# main.net
KiCad netlist of a schematic drawn in EAGLE
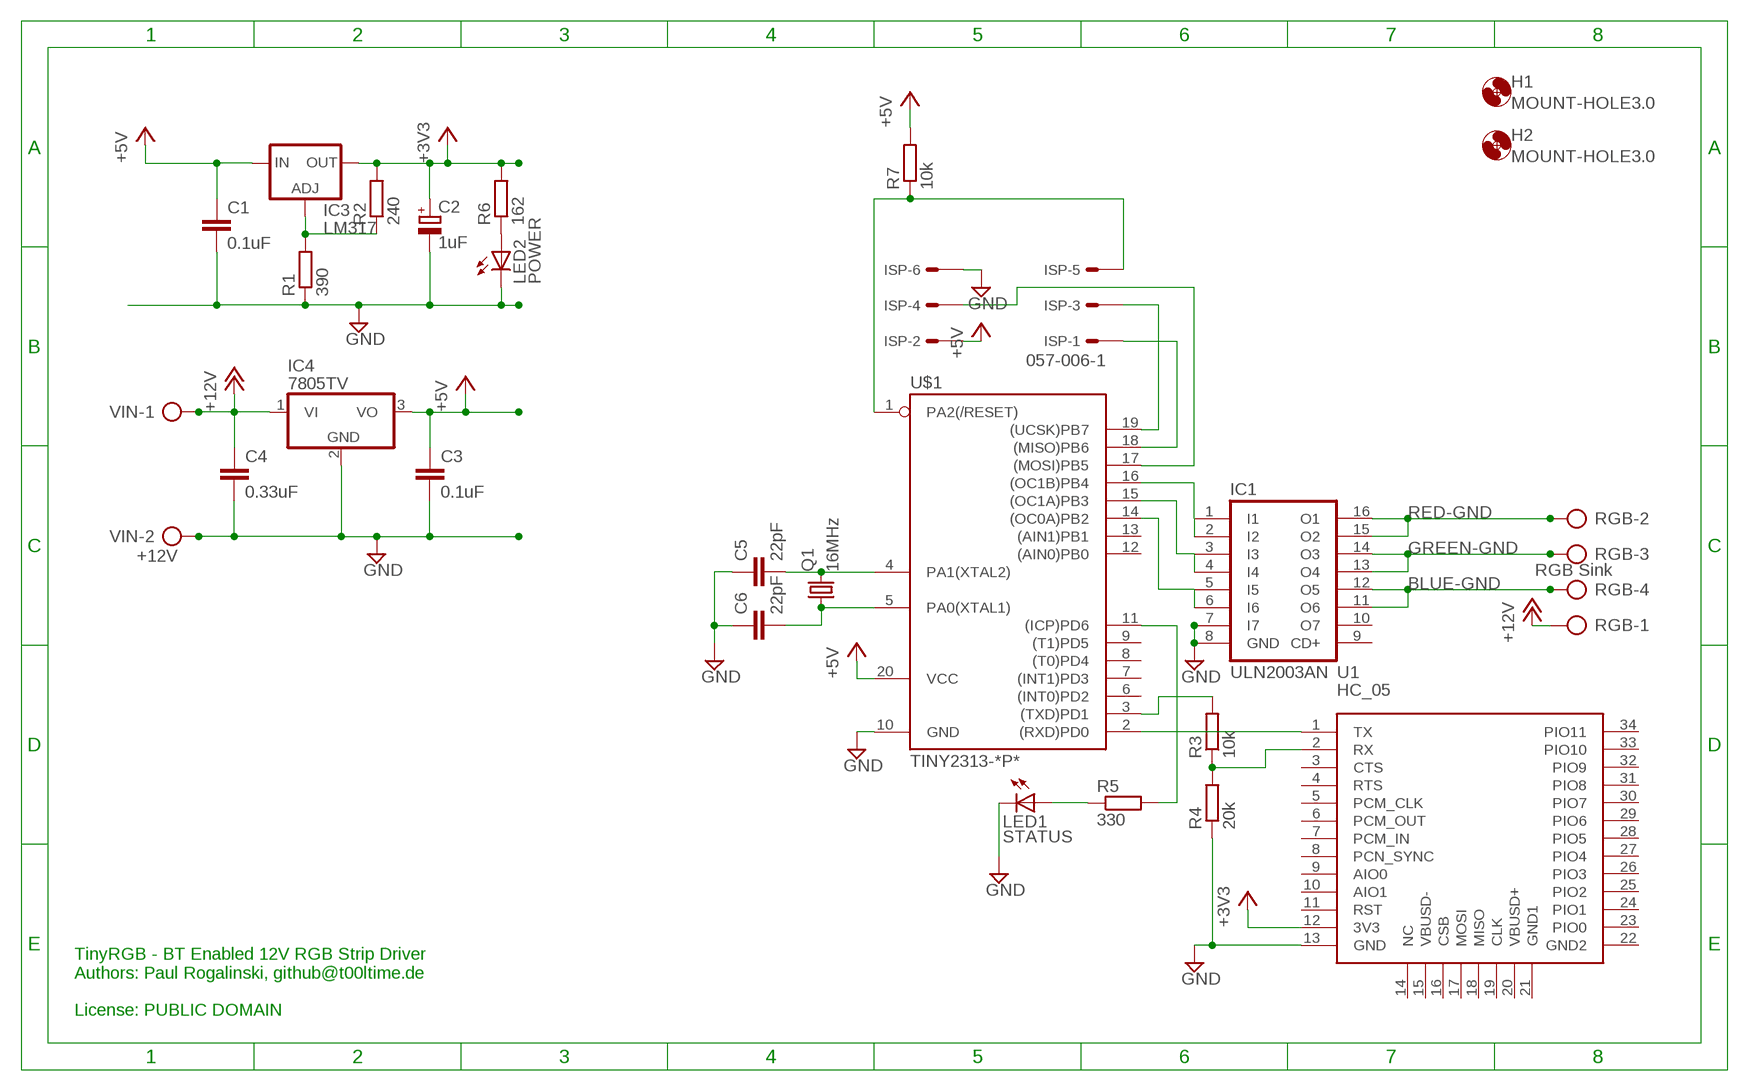
[diagram p0: schematic, sheet 1]

(export (version "E")
  (design (tool "Eeschema 10.0.6"))
  (components
    (comp (ref "C1")
      (value "0.1uF")
      (footprint "eagle-import:C025-025X050")
      (libsource (lib "eagle-import") (part "C-EU025-025X050"))
    )
    (comp (ref "C2")
      (value "1uF")
      (footprint "eagle-import:E2-5")
      (libsource (lib "eagle-import") (part "CPOL-EUE2-5"))
    )
    (comp (ref "C3")
      (value "0.1uF")
      (footprint "eagle-import:C025-025X050")
      (libsource (lib "eagle-import") (part "C-EU025-025X050"))
    )
    (comp (ref "C4")
      (value "0.33uF")
      (footprint "eagle-import:C025_050-025X075")
      (libsource (lib "eagle-import") (part "C-EU025_050-025X075"))
    )
    (comp (ref "C5")
      (value "22pF")
      (footprint "eagle-import:C025-024X044")
      (libsource (lib "eagle-import") (part "C-EU025-024X044"))
    )
    (comp (ref "C6")
      (value "22pF")
      (footprint "eagle-import:C025-024X044")
      (libsource (lib "eagle-import") (part "C-EU025-024X044"))
    )
    (comp (ref "H1")
      (value "MOUNT-HOLE3.0")
      (footprint "eagle-import:3,0")
      (libsource (lib "eagle-import") (part "MOUNT-HOLE3.0"))
    )
    (comp (ref "H2")
      (value "MOUNT-HOLE3.0")
      (footprint "eagle-import:3,0")
      (libsource (lib "eagle-import") (part "MOUNT-HOLE3.0"))
    )
    (comp (ref "IC1")
      (value "ULN2003AN")
      (footprint "eagle-import:DIL16")
      (libsource (lib "eagle-import") (part "ULN2003AN"))
    )
    (comp (ref "IC3")
      (value "LM317")
      (footprint "eagle-import:317L")
      (libsource (lib "eagle-import") (part "LM317L"))
    )
    (comp (ref "IC4")
      (value "7805TV")
      (footprint "eagle-import:TO220V")
      (libsource (lib "eagle-import") (part "78TV05"))
    )
    (comp (ref "ISP")
      (value "057-006-1")
      (footprint "eagle-import:057-006-1")
      (libsource (lib "eagle-import") (part "057-006-1"))
    )
    (comp (ref "LED1")
      (value "STATUS")
      (footprint "eagle-import:LED3MM")
      (libsource (lib "eagle-import") (part "LED3MM"))
    )
    (comp (ref "LED2")
      (value "POWER")
      (footprint "eagle-import:LED3MM")
      (libsource (lib "eagle-import") (part "LED3MM"))
    )
    (comp (ref "Q1")
      (value "16MHz")
      (footprint "eagle-import:HC49U-V")
      (libsource (lib "eagle-import") (part "CRYSTALHC49U-V"))
    )
    (comp (ref "R1")
      (value "390")
      (footprint "eagle-import:0207_5V")
      (libsource (lib "eagle-import") (part "R-EU_0207/5V"))
    )
    (comp (ref "R2")
      (value "240")
      (footprint "eagle-import:0207_5V")
      (libsource (lib "eagle-import") (part "R-EU_0207/5V"))
    )
    (comp (ref "R3")
      (value "10k")
      (footprint "eagle-import:0207_5V")
      (libsource (lib "eagle-import") (part "R-EU_0207/5V"))
    )
    (comp (ref "R4")
      (value "20k")
      (footprint "eagle-import:0207_5V")
      (libsource (lib "eagle-import") (part "R-EU_0207/5V"))
    )
    (comp (ref "R5")
      (value "330")
      (footprint "eagle-import:0207_5V")
      (libsource (lib "eagle-import") (part "R-EU_0207/5V"))
    )
    (comp (ref "R6")
      (value "162")
      (footprint "eagle-import:0207_5V")
      (libsource (lib "eagle-import") (part "R-EU_0207/5V"))
    )
    (comp (ref "R7")
      (value "10k")
      (footprint "eagle-import:0207_5V")
      (libsource (lib "eagle-import") (part "R-EU_0207/5V"))
    )
    (comp (ref "RGB")
      (value "RGB Sink")
      (footprint "eagle-import:AK500_4")
      (libsource (lib "eagle-import") (part "AK500/4"))
    )
    (comp (ref "U$1")
      (value "TINY2313-*P*")
      (footprint "eagle-import:DIL20")
      (libsource (lib "eagle-import") (part "TINY2313-P"))
    )
    (comp (ref "U1")
      (value "HC_05")
      (footprint "eagle-import:BLUETOOTH_SMD")
      (libsource (lib "eagle-import") (part "HC_05"))
    )
    (comp (ref "VIN")
      (value "+12V")
      (footprint "eagle-import:AK500_2")
      (libsource (lib "eagle-import") (part "AK500/2"))
    )
  )
  (nets
    (net (code "1") (name "+3V3") (class "Default")
      (node (ref "C2") (pin "+") (pinfunction "+_+") (pintype "passive"))
      (node (ref "IC3") (pin "2") (pinfunction "OUT_2") (pintype "passive"))
      (node (ref "R2") (pin "2") (pinfunction "2_2") (pintype "passive"))
      (node (ref "R6") (pin "2") (pinfunction "2_2") (pintype "passive"))
      (node (ref "U1") (pin "12") (pinfunction "3V3_12") (pintype "bidirectional"))
    )
    (net (code "2") (name "+5V") (class "Default")
      (node (ref "C1") (pin "1") (pinfunction "1_1") (pintype "passive"))
      (node (ref "C3") (pin "1") (pinfunction "1_1") (pintype "passive"))
      (node (ref "IC3") (pin "3") (pinfunction "IN_3") (pintype "input"))
      (node (ref "IC4") (pin "3") (pinfunction "VO_3") (pintype "passive"))
      (node (ref "ISP") (pin "2") (pinfunction "S_2") (pintype "passive"))
      (node (ref "R7") (pin "2") (pinfunction "2_2") (pintype "passive"))
      (node (ref "U$1") (pin "20") (pinfunction "VCC_20") (pintype "power_in"))
    )
    (net (code "3") (name "+12V") (class "Default")
      (node (ref "C4") (pin "1") (pinfunction "1_1") (pintype "passive"))
      (node (ref "IC4") (pin "1") (pinfunction "VI_1") (pintype "input"))
      (node (ref "RGB") (pin "1") (pinfunction "KL_1") (pintype "passive"))
      (node (ref "VIN") (pin "1") (pinfunction "KL_1") (pintype "passive"))
    )
    (net (code "4") (name "/BLUE-GND") (class "Default")
      (node (ref "IC1") (pin "11") (pinfunction "O6_11") (pintype "open_collector"))
      (node (ref "IC1") (pin "12") (pinfunction "O5_12") (pintype "open_collector"))
      (node (ref "RGB") (pin "4") (pinfunction "KL_4") (pintype "passive"))
    )
    (net (code "5") (name "/GREEN-GND") (class "Default")
      (node (ref "IC1") (pin "13") (pinfunction "O4_13") (pintype "open_collector"))
      (node (ref "IC1") (pin "14") (pinfunction "O3_14") (pintype "open_collector"))
      (node (ref "RGB") (pin "3") (pinfunction "KL_3") (pintype "passive"))
    )
    (net (code "6") (name "/RED-GND") (class "Default")
      (node (ref "IC1") (pin "15") (pinfunction "O2_15") (pintype "open_collector"))
      (node (ref "IC1") (pin "16") (pinfunction "O1_16") (pintype "open_collector"))
      (node (ref "RGB") (pin "2") (pinfunction "KL_2") (pintype "passive"))
    )
    (net (code "7") (name "GND") (class "Default")
      (node (ref "C1") (pin "2") (pinfunction "2_2") (pintype "passive"))
      (node (ref "C2") (pin "-") (pinfunction "-_-") (pintype "passive"))
      (node (ref "C3") (pin "2") (pinfunction "2_2") (pintype "passive"))
      (node (ref "C4") (pin "2") (pinfunction "2_2") (pintype "passive"))
      (node (ref "C5") (pin "1") (pinfunction "1_1") (pintype "passive"))
      (node (ref "C6") (pin "1") (pinfunction "1_1") (pintype "passive"))
      (node (ref "IC1") (pin "7") (pinfunction "I7_7") (pintype "input"))
      (node (ref "IC1") (pin "8") (pinfunction "GND_8") (pintype "power_in"))
      (node (ref "IC4") (pin "2") (pinfunction "GND_2") (pintype "passive"))
      (node (ref "ISP") (pin "6") (pinfunction "S_6") (pintype "passive"))
      (node (ref "LED1") (pin "K") (pinfunction "C_K") (pintype "passive"))
      (node (ref "LED2") (pin "K") (pinfunction "C_K") (pintype "passive"))
      (node (ref "R1") (pin "1") (pinfunction "1_1") (pintype "passive"))
      (node (ref "R4") (pin "1") (pinfunction "1_1") (pintype "passive"))
      (node (ref "U$1") (pin "10") (pinfunction "GND_10") (pintype "power_in"))
      (node (ref "U1") (pin "13") (pinfunction "GND_13") (pintype "bidirectional"))
      (node (ref "VIN") (pin "2") (pinfunction "KL_2") (pintype "passive"))
    )
    (net (code "8") (name "Net-(IC1-I1)") (class "Default")
      (node (ref "IC1") (pin "1") (pinfunction "I1_1") (pintype "input"))
      (node (ref "IC1") (pin "2") (pinfunction "I2_2") (pintype "input"))
      (node (ref "U$1") (pin "16") (pinfunction "(OC1B)PB4_16") (pintype "bidirectional"))
    )
    (net (code "9") (name "Net-(IC1-I3)") (class "Default")
      (node (ref "IC1") (pin "3") (pinfunction "I3_3") (pintype "input"))
      (node (ref "IC1") (pin "4") (pinfunction "I4_4") (pintype "input"))
      (node (ref "U$1") (pin "15") (pinfunction "(OC1A)PB3_15") (pintype "bidirectional"))
    )
    (net (code "10") (name "Net-(IC1-I5)") (class "Default")
      (node (ref "IC1") (pin "5") (pinfunction "I5_5") (pintype "input"))
      (node (ref "IC1") (pin "6") (pinfunction "I6_6") (pintype "input"))
      (node (ref "U$1") (pin "14") (pinfunction "(OC0A)PB2_14") (pintype "bidirectional"))
    )
    (net (code "11") (name "Net-(IC3-ADJ)") (class "Default")
      (node (ref "IC3") (pin "1") (pinfunction "ADJ_1") (pintype "input"))
      (node (ref "R1") (pin "2") (pinfunction "2_2") (pintype "passive"))
      (node (ref "R2") (pin "1") (pinfunction "1_1") (pintype "passive"))
    )
    (net (code "12") (name "Net-(ISPA-S)") (class "Default")
      (node (ref "ISP") (pin "1") (pinfunction "S_1") (pintype "passive"))
      (node (ref "U$1") (pin "18") (pinfunction "(MISO)PB6_18") (pintype "bidirectional"))
    )
    (net (code "13") (name "Net-(ISPC-S)") (class "Default")
      (node (ref "ISP") (pin "3") (pinfunction "S_3") (pintype "passive"))
      (node (ref "U$1") (pin "19") (pinfunction "(UCSK)PB7_19") (pintype "bidirectional"))
    )
    (net (code "14") (name "Net-(ISPD-S)") (class "Default")
      (node (ref "ISP") (pin "4") (pinfunction "S_4") (pintype "passive"))
      (node (ref "U$1") (pin "17") (pinfunction "(MOSI)PB5_17") (pintype "bidirectional"))
    )
    (net (code "15") (name "Net-(ISPE-S)") (class "Default")
      (node (ref "ISP") (pin "5") (pinfunction "S_5") (pintype "passive"))
      (node (ref "R7") (pin "1") (pinfunction "1_1") (pintype "passive"))
      (node (ref "U$1") (pin "1") (pinfunction "PA2(/RESET)_1") (pintype "input"))
    )
    (net (code "16") (name "Net-(LED1-PadA)") (class "Default")
      (node (ref "LED1") (pin "A") (pinfunction "A_A") (pintype "passive"))
      (node (ref "R5") (pin "1") (pinfunction "1_1") (pintype "passive"))
    )
    (net (code "17") (name "Net-(LED2-PadA)") (class "Default")
      (node (ref "LED2") (pin "A") (pinfunction "A_A") (pintype "passive"))
      (node (ref "R6") (pin "1") (pinfunction "1_1") (pintype "passive"))
    )
    (net (code "18") (name "Net-(U$1-(ICP)PD6)") (class "Default")
      (node (ref "R5") (pin "2") (pinfunction "2_2") (pintype "passive"))
      (node (ref "U$1") (pin "11") (pinfunction "(ICP)PD6_11") (pintype "bidirectional"))
    )
    (net (code "19") (name "Net-(U$1-(RXD)PD0)") (class "Default")
      (node (ref "U$1") (pin "2") (pinfunction "(RXD)PD0_2") (pintype "bidirectional"))
      (node (ref "U1") (pin "1") (pinfunction "TX_1") (pintype "bidirectional"))
    )
    (net (code "20") (name "Net-(U$1-(TXD)PD1)") (class "Default")
      (node (ref "R3") (pin "2") (pinfunction "2_2") (pintype "passive"))
      (node (ref "U$1") (pin "3") (pinfunction "(TXD)PD1_3") (pintype "bidirectional"))
    )
    (net (code "21") (name "Net-(U$1-PA0(XTAL1))") (class "Default")
      (node (ref "C6") (pin "2") (pinfunction "2_2") (pintype "passive"))
      (node (ref "Q1") (pin "1") (pinfunction "1_1") (pintype "passive"))
      (node (ref "U$1") (pin "5") (pinfunction "PA0(XTAL1)_5") (pintype "bidirectional"))
    )
    (net (code "22") (name "Net-(U$1-PA1(XTAL2))") (class "Default")
      (node (ref "C5") (pin "2") (pinfunction "2_2") (pintype "passive"))
      (node (ref "Q1") (pin "2") (pinfunction "2_2") (pintype "passive"))
      (node (ref "U$1") (pin "4") (pinfunction "PA1(XTAL2)_4") (pintype "bidirectional"))
    )
    (net (code "23") (name "Net-(U1-RX)") (class "Default")
      (node (ref "R3") (pin "1") (pinfunction "1_1") (pintype "passive"))
      (node (ref "R4") (pin "2") (pinfunction "2_2") (pintype "passive"))
      (node (ref "U1") (pin "2") (pinfunction "RX_2") (pintype "bidirectional"))
    )
    (net (code "24") (name "unconnected-(IC1-CD+-Pad9)") (class "Default")
      (node (ref "IC1") (pin "9") (pinfunction "CD+_9") (pintype "passive"))
    )
    (net (code "25") (name "unconnected-(IC1-O7-Pad10)") (class "Default")
      (node (ref "IC1") (pin "10") (pinfunction "O7_10") (pintype "open_collector"))
    )
    (net (code "26") (name "unconnected-(U$1-(AIN0)PB0-Pad12)") (class "Default")
      (node (ref "U$1") (pin "12") (pinfunction "(AIN0)PB0_12") (pintype "bidirectional"))
    )
    (net (code "27") (name "unconnected-(U$1-(AIN1)PB1-Pad13)") (class "Default")
      (node (ref "U$1") (pin "13") (pinfunction "(AIN1)PB1_13") (pintype "bidirectional"))
    )
    (net (code "28") (name "unconnected-(U$1-(INT0)PD2-Pad6)") (class "Default")
      (node (ref "U$1") (pin "6") (pinfunction "(INT0)PD2_6") (pintype "bidirectional"))
    )
    (net (code "29") (name "unconnected-(U$1-(INT1)PD3-Pad7)") (class "Default")
      (node (ref "U$1") (pin "7") (pinfunction "(INT1)PD3_7") (pintype "bidirectional"))
    )
    (net (code "30") (name "unconnected-(U$1-(T0)PD4-Pad8)") (class "Default")
      (node (ref "U$1") (pin "8") (pinfunction "(T0)PD4_8") (pintype "bidirectional"))
    )
    (net (code "31") (name "unconnected-(U$1-(T1)PD5-Pad9)") (class "Default")
      (node (ref "U$1") (pin "9") (pinfunction "(T1)PD5_9") (pintype "bidirectional"))
    )
    (net (code "32") (name "unconnected-(U1-AIO0-Pad9)") (class "Default")
      (node (ref "U1") (pin "9") (pinfunction "AIO0_9") (pintype "bidirectional"))
    )
    (net (code "33") (name "unconnected-(U1-AIO1-Pad10)") (class "Default")
      (node (ref "U1") (pin "10") (pinfunction "AIO1_10") (pintype "bidirectional"))
    )
    (net (code "34") (name "unconnected-(U1-CLK-Pad19)") (class "Default")
      (node (ref "U1") (pin "19") (pinfunction "CLK_19") (pintype "bidirectional"))
    )
    (net (code "35") (name "unconnected-(U1-CSB-Pad16)") (class "Default")
      (node (ref "U1") (pin "16") (pinfunction "CSB_16") (pintype "bidirectional"))
    )
    (net (code "36") (name "unconnected-(U1-CTS-Pad3)") (class "Default")
      (node (ref "U1") (pin "3") (pinfunction "CTS_3") (pintype "bidirectional"))
    )
    (net (code "37") (name "unconnected-(U1-GND1-Pad21)") (class "Default")
      (node (ref "U1") (pin "21") (pinfunction "GND1_21") (pintype "bidirectional"))
    )
    (net (code "38") (name "unconnected-(U1-GND2-Pad22)") (class "Default")
      (node (ref "U1") (pin "22") (pinfunction "GND2_22") (pintype "bidirectional"))
    )
    (net (code "39") (name "unconnected-(U1-MISO-Pad18)") (class "Default")
      (node (ref "U1") (pin "18") (pinfunction "MISO_18") (pintype "bidirectional"))
    )
    (net (code "40") (name "unconnected-(U1-MOSI-Pad17)") (class "Default")
      (node (ref "U1") (pin "17") (pinfunction "MOSI_17") (pintype "bidirectional"))
    )
    (net (code "41") (name "unconnected-(U1-NC-Pad14)") (class "Default")
      (node (ref "U1") (pin "14") (pinfunction "NC_14") (pintype "bidirectional"))
    )
    (net (code "42") (name "unconnected-(U1-PCM_CLK-Pad5)") (class "Default")
      (node (ref "U1") (pin "5") (pinfunction "PCM_CLK_5") (pintype "bidirectional"))
    )
    (net (code "43") (name "unconnected-(U1-PCM_IN-Pad7)") (class "Default")
      (node (ref "U1") (pin "7") (pinfunction "PCM_IN_7") (pintype "bidirectional"))
    )
    (net (code "44") (name "unconnected-(U1-PCM_OUT-Pad6)") (class "Default")
      (node (ref "U1") (pin "6") (pinfunction "PCM_OUT_6") (pintype "bidirectional"))
    )
    (net (code "45") (name "unconnected-(U1-PCN_SYNC-Pad8)") (class "Default")
      (node (ref "U1") (pin "8") (pinfunction "PCN_SYNC_8") (pintype "bidirectional"))
    )
    (net (code "46") (name "unconnected-(U1-PIO0-Pad23)") (class "Default")
      (node (ref "U1") (pin "23") (pinfunction "PIO0_23") (pintype "bidirectional"))
    )
    (net (code "47") (name "unconnected-(U1-PIO1-Pad24)") (class "Default")
      (node (ref "U1") (pin "24") (pinfunction "PIO1_24") (pintype "bidirectional"))
    )
    (net (code "48") (name "unconnected-(U1-PIO2-Pad25)") (class "Default")
      (node (ref "U1") (pin "25") (pinfunction "PIO2_25") (pintype "bidirectional"))
    )
    (net (code "49") (name "unconnected-(U1-PIO3-Pad26)") (class "Default")
      (node (ref "U1") (pin "26") (pinfunction "PIO3_26") (pintype "bidirectional"))
    )
    (net (code "50") (name "unconnected-(U1-PIO4-Pad27)") (class "Default")
      (node (ref "U1") (pin "27") (pinfunction "PIO4_27") (pintype "bidirectional"))
    )
    (net (code "51") (name "unconnected-(U1-PIO5-Pad28)") (class "Default")
      (node (ref "U1") (pin "28") (pinfunction "PIO5_28") (pintype "bidirectional"))
    )
    (net (code "52") (name "unconnected-(U1-PIO6-Pad29)") (class "Default")
      (node (ref "U1") (pin "29") (pinfunction "PIO6_29") (pintype "bidirectional"))
    )
    (net (code "53") (name "unconnected-(U1-PIO7-Pad30)") (class "Default")
      (node (ref "U1") (pin "30") (pinfunction "PIO7_30") (pintype "bidirectional"))
    )
    (net (code "54") (name "unconnected-(U1-PIO8-Pad31)") (class "Default")
      (node (ref "U1") (pin "31") (pinfunction "PIO8_31") (pintype "bidirectional"))
    )
    (net (code "55") (name "unconnected-(U1-PIO9-Pad32)") (class "Default")
      (node (ref "U1") (pin "32") (pinfunction "PIO9_32") (pintype "bidirectional"))
    )
    (net (code "56") (name "unconnected-(U1-PIO10-Pad33)") (class "Default")
      (node (ref "U1") (pin "33") (pinfunction "PIO10_33") (pintype "bidirectional"))
    )
    (net (code "57") (name "unconnected-(U1-PIO11-Pad34)") (class "Default")
      (node (ref "U1") (pin "34") (pinfunction "PIO11_34") (pintype "bidirectional"))
    )
    (net (code "58") (name "unconnected-(U1-RST-Pad11)") (class "Default")
      (node (ref "U1") (pin "11") (pinfunction "RST_11") (pintype "bidirectional"))
    )
    (net (code "59") (name "unconnected-(U1-RTS-Pad4)") (class "Default")
      (node (ref "U1") (pin "4") (pinfunction "RTS_4") (pintype "bidirectional"))
    )
    (net (code "60") (name "unconnected-(U1-VBUSD+-Pad20)") (class "Default")
      (node (ref "U1") (pin "20") (pinfunction "VBUSD+_20") (pintype "bidirectional"))
    )
    (net (code "61") (name "unconnected-(U1-VBUSD--Pad15)") (class "Default")
      (node (ref "U1") (pin "15") (pinfunction "VBUSD-_15") (pintype "bidirectional"))
    )
  )
)
